# samd11-usb-test.net
KiCad netlist of a schematic drawn in EAGLE
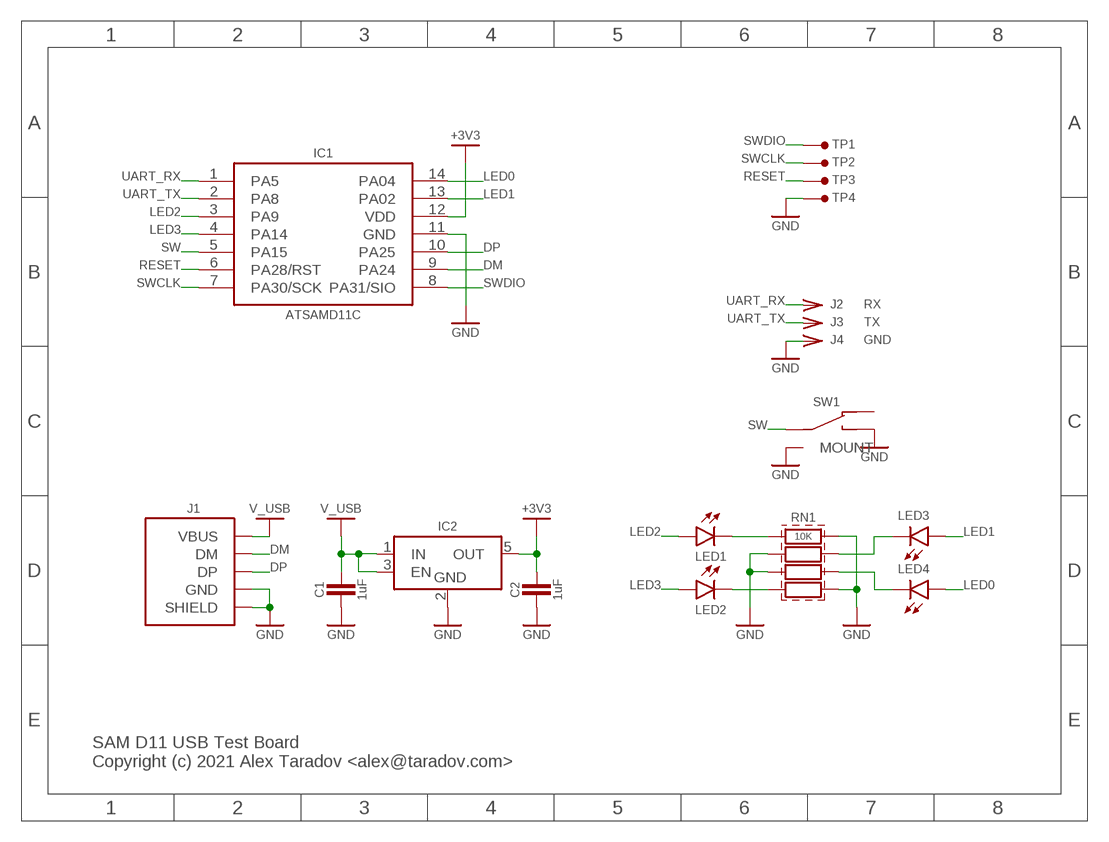
[diagram p0: schematic, sheet 1]

(export (version "E")
  (design (tool "Eeschema 10.0.6"))
  (components
    (comp (ref "C1")
      (value "1uF")
      (footprint "eagle-import:SMD0603")
      (libsource (lib "eagle-import") (part "C-0603"))
    )
    (comp (ref "C2")
      (value "1uF")
      (footprint "eagle-import:SMD0603")
      (libsource (lib "eagle-import") (part "C-0603"))
    )
    (comp (ref "IC1")
      (value "ATSAMD11C")
      (footprint "eagle-import:SO-14")
      (libsource (lib "eagle-import") (part "ATSAMD11C"))
    )
    (comp (ref "IC2")
      (value "MIC5504-SOT23-5")
      (footprint "eagle-import:SOT23-5")
      (libsource (lib "eagle-import") (part "MIC5504-SOT23-5"))
    )
    (comp (ref "J1")
      (value "USB-A-PLUG-TH-NM")
      (footprint "eagle-import:USB-A-PLUG-TH-NM")
      (libsource (lib "eagle-import") (part "USB-A-PLUG-TH-NM"))
    )
    (comp (ref "J2")
      (value "RX")
      (footprint "eagle-import:PIN-TH")
      (libsource (lib "eagle-import") (part "CONN-SINGLE-TH"))
    )
    (comp (ref "J3")
      (value "TX")
      (footprint "eagle-import:PIN-TH")
      (libsource (lib "eagle-import") (part "CONN-SINGLE-TH"))
    )
    (comp (ref "J4")
      (value "GND")
      (footprint "eagle-import:PIN-TH")
      (libsource (lib "eagle-import") (part "CONN-SINGLE-TH"))
    )
    (comp (ref "LED1")
      (value "LED_SMDLED_0603")
      (footprint "eagle-import:SMD0603")
      (libsource (lib "eagle-import") (part "LED_SMDLED_0603"))
    )
    (comp (ref "LED2")
      (value "LED_SMDLED_0603")
      (footprint "eagle-import:SMD0603")
      (libsource (lib "eagle-import") (part "LED_SMDLED_0603"))
    )
    (comp (ref "LED3")
      (value "LED_SMDLED_0603")
      (footprint "eagle-import:SMD0603")
      (libsource (lib "eagle-import") (part "LED_SMDLED_0603"))
    )
    (comp (ref "LED4")
      (value "LED_SMDLED_0603")
      (footprint "eagle-import:SMD0603")
      (libsource (lib "eagle-import") (part "LED_SMDLED_0603"))
    )
    (comp (ref "RN1")
      (value "10K")
      (footprint "eagle-import:SMD0603-X4")
      (libsource (lib "eagle-import") (part "RN-4-0603-X4"))
    )
    (comp (ref "SW1")
      (value "SPDT_SWITCH-MOUNT-SMD-MOUNT-NO-HOLES")
      (footprint "eagle-import:SPDT-SMD-5MM-NO-HOLES")
      (libsource (lib "eagle-import") (part "SPDT_SWITCH-MOUNT-SMD-MOUNT-NO-HOLES"))
    )
    (comp (ref "TP1")
      (value "TEST-POINT-1.27MM-TH")
      (footprint "eagle-import:TP-1.27MM-TH")
      (libsource (lib "eagle-import") (part "TEST-POINT-1.27MM-TH"))
    )
    (comp (ref "TP2")
      (value "TEST-POINT-1.27MM-TH")
      (footprint "eagle-import:TP-1.27MM-TH")
      (libsource (lib "eagle-import") (part "TEST-POINT-1.27MM-TH"))
    )
    (comp (ref "TP3")
      (value "TEST-POINT-1.27MM-TH")
      (footprint "eagle-import:TP-1.27MM-TH")
      (libsource (lib "eagle-import") (part "TEST-POINT-1.27MM-TH"))
    )
    (comp (ref "TP4")
      (value "TEST-POINT-1.27MM-TH")
      (footprint "eagle-import:TP-1.27MM-TH")
      (libsource (lib "eagle-import") (part "TEST-POINT-1.27MM-TH"))
    )
  )
  (nets
    (net (code "1") (name "+3V3") (class "Default")
      (node (ref "C2") (pin "2") (pinfunction "2_2") (pintype "passive"))
      (node (ref "IC1") (pin "12") (pinfunction "VDD_12") (pintype "bidirectional"))
      (node (ref "IC2") (pin "5") (pinfunction "OUT_5") (pintype "passive"))
    )
    (net (code "2") (name "/DM") (class "Default")
      (node (ref "IC1") (pin "9") (pinfunction "PA24_9") (pintype "bidirectional"))
      (node (ref "J1") (pin "2") (pinfunction "DM_2") (pintype "passive"))
    )
    (net (code "3") (name "/DP") (class "Default")
      (node (ref "IC1") (pin "10") (pinfunction "PA25_10") (pintype "bidirectional"))
      (node (ref "J1") (pin "3") (pinfunction "DP_3") (pintype "passive"))
    )
    (net (code "4") (name "/LED0") (class "Default")
      (node (ref "IC1") (pin "14") (pinfunction "PA04_14") (pintype "bidirectional"))
      (node (ref "LED4") (pin "1") (pinfunction "A_1") (pintype "passive"))
    )
    (net (code "5") (name "/LED1") (class "Default")
      (node (ref "IC1") (pin "13") (pinfunction "PA02_13") (pintype "bidirectional"))
      (node (ref "LED3") (pin "1") (pinfunction "A_1") (pintype "passive"))
    )
    (net (code "6") (name "/LED2") (class "Default")
      (node (ref "IC1") (pin "3") (pinfunction "PA9_3") (pintype "bidirectional"))
      (node (ref "LED1") (pin "1") (pinfunction "A_1") (pintype "passive"))
    )
    (net (code "7") (name "/LED3") (class "Default")
      (node (ref "IC1") (pin "4") (pinfunction "PA14_4") (pintype "bidirectional"))
      (node (ref "LED2") (pin "1") (pinfunction "A_1") (pintype "passive"))
    )
    (net (code "8") (name "/RESET") (class "Default")
      (node (ref "IC1") (pin "6") (pinfunction "PA28/RST_6") (pintype "bidirectional"))
      (node (ref "TP3") (pin "1") (pinfunction "1_1") (pintype "passive"))
    )
    (net (code "9") (name "/SW") (class "Default")
      (node (ref "IC1") (pin "5") (pinfunction "PA15_5") (pintype "bidirectional"))
      (node (ref "SW1") (pin "C") (pinfunction "C_C") (pintype "passive"))
    )
    (net (code "10") (name "/SWCLK") (class "Default")
      (node (ref "IC1") (pin "7") (pinfunction "PA30/SCK_7") (pintype "bidirectional"))
      (node (ref "TP2") (pin "1") (pinfunction "1_1") (pintype "passive"))
    )
    (net (code "11") (name "/SWDIO") (class "Default")
      (node (ref "IC1") (pin "8") (pinfunction "PA31/SIO_8") (pintype "bidirectional"))
      (node (ref "TP1") (pin "1") (pinfunction "1_1") (pintype "passive"))
    )
    (net (code "12") (name "/UART_RX") (class "Default")
      (node (ref "IC1") (pin "1") (pinfunction "PA5_1") (pintype "bidirectional"))
      (node (ref "J2") (pin "1") (pinfunction "1_1") (pintype "passive"))
    )
    (net (code "13") (name "/UART_TX") (class "Default")
      (node (ref "IC1") (pin "2") (pinfunction "PA8_2") (pintype "bidirectional"))
      (node (ref "J3") (pin "1") (pinfunction "1_1") (pintype "passive"))
    )
    (net (code "14") (name "GND") (class "Default")
      (node (ref "C1") (pin "1") (pinfunction "1_1") (pintype "passive"))
      (node (ref "C2") (pin "1") (pinfunction "1_1") (pintype "passive"))
      (node (ref "IC1") (pin "11") (pinfunction "GND_11") (pintype "bidirectional"))
      (node (ref "IC2") (pin "2") (pinfunction "GND_2") (pintype "passive"))
      (node (ref "J1") (pin "4") (pinfunction "GND_4") (pintype "passive"))
      (node (ref "J1") (pin "M1") (pinfunction "SHIELD_M1") (pintype "passive"))
      (node (ref "J1") (pin "M2") (pinfunction "SHIELD_M2") (pintype "passive"))
      (node (ref "J4") (pin "1") (pinfunction "1_1") (pintype "passive"))
      (node (ref "RN1") (pin "2") (pinfunction "2_2") (pintype "passive"))
      (node (ref "RN1") (pin "3") (pinfunction "3_3") (pintype "passive"))
      (node (ref "RN1") (pin "5") (pinfunction "5_5") (pintype "passive"))
      (node (ref "RN1") (pin "8") (pinfunction "8_8") (pintype "passive"))
      (node (ref "SW1") (pin "B") (pinfunction "B_B") (pintype "passive"))
      (node (ref "SW1") (pin "M0") (pinfunction "MOUNT_M0") (pintype "passive"))
      (node (ref "SW1") (pin "M1") (pinfunction "MOUNT_M1") (pintype "passive"))
      (node (ref "SW1") (pin "M2") (pinfunction "MOUNT_M2") (pintype "passive"))
      (node (ref "SW1") (pin "M3") (pinfunction "MOUNT_M3") (pintype "passive"))
      (node (ref "TP4") (pin "1") (pinfunction "1_1") (pintype "passive"))
    )
    (net (code "15") (name "Net-(LED1-C)") (class "Default")
      (node (ref "LED1") (pin "2") (pinfunction "C_2") (pintype "passive"))
      (node (ref "RN1") (pin "1") (pinfunction "1_1") (pintype "passive"))
    )
    (net (code "16") (name "Net-(LED2-C)") (class "Default")
      (node (ref "LED2") (pin "2") (pinfunction "C_2") (pintype "passive"))
      (node (ref "RN1") (pin "4") (pinfunction "4_4") (pintype "passive"))
    )
    (net (code "17") (name "Net-(LED3-C)") (class "Default")
      (node (ref "LED3") (pin "2") (pinfunction "C_2") (pintype "passive"))
      (node (ref "RN1") (pin "7") (pinfunction "7_7") (pintype "passive"))
    )
    (net (code "18") (name "Net-(LED4-C)") (class "Default")
      (node (ref "LED4") (pin "2") (pinfunction "C_2") (pintype "passive"))
      (node (ref "RN1") (pin "6") (pinfunction "6_6") (pintype "passive"))
    )
    (net (code "19") (name "V_USB") (class "Default")
      (node (ref "C1") (pin "2") (pinfunction "2_2") (pintype "passive"))
      (node (ref "IC2") (pin "1") (pinfunction "IN_1") (pintype "passive"))
      (node (ref "IC2") (pin "3") (pinfunction "EN_3") (pintype "passive"))
      (node (ref "J1") (pin "1") (pinfunction "VBUS_1") (pintype "passive"))
    )
    (net (code "20") (name "unconnected-(SW1-PadA)") (class "Default")
      (node (ref "SW1") (pin "A") (pinfunction "A_A") (pintype "passive"))
    )
  )
)
